# delayed_pulser.net
KiCad netlist of a schematic drawn in EAGLE
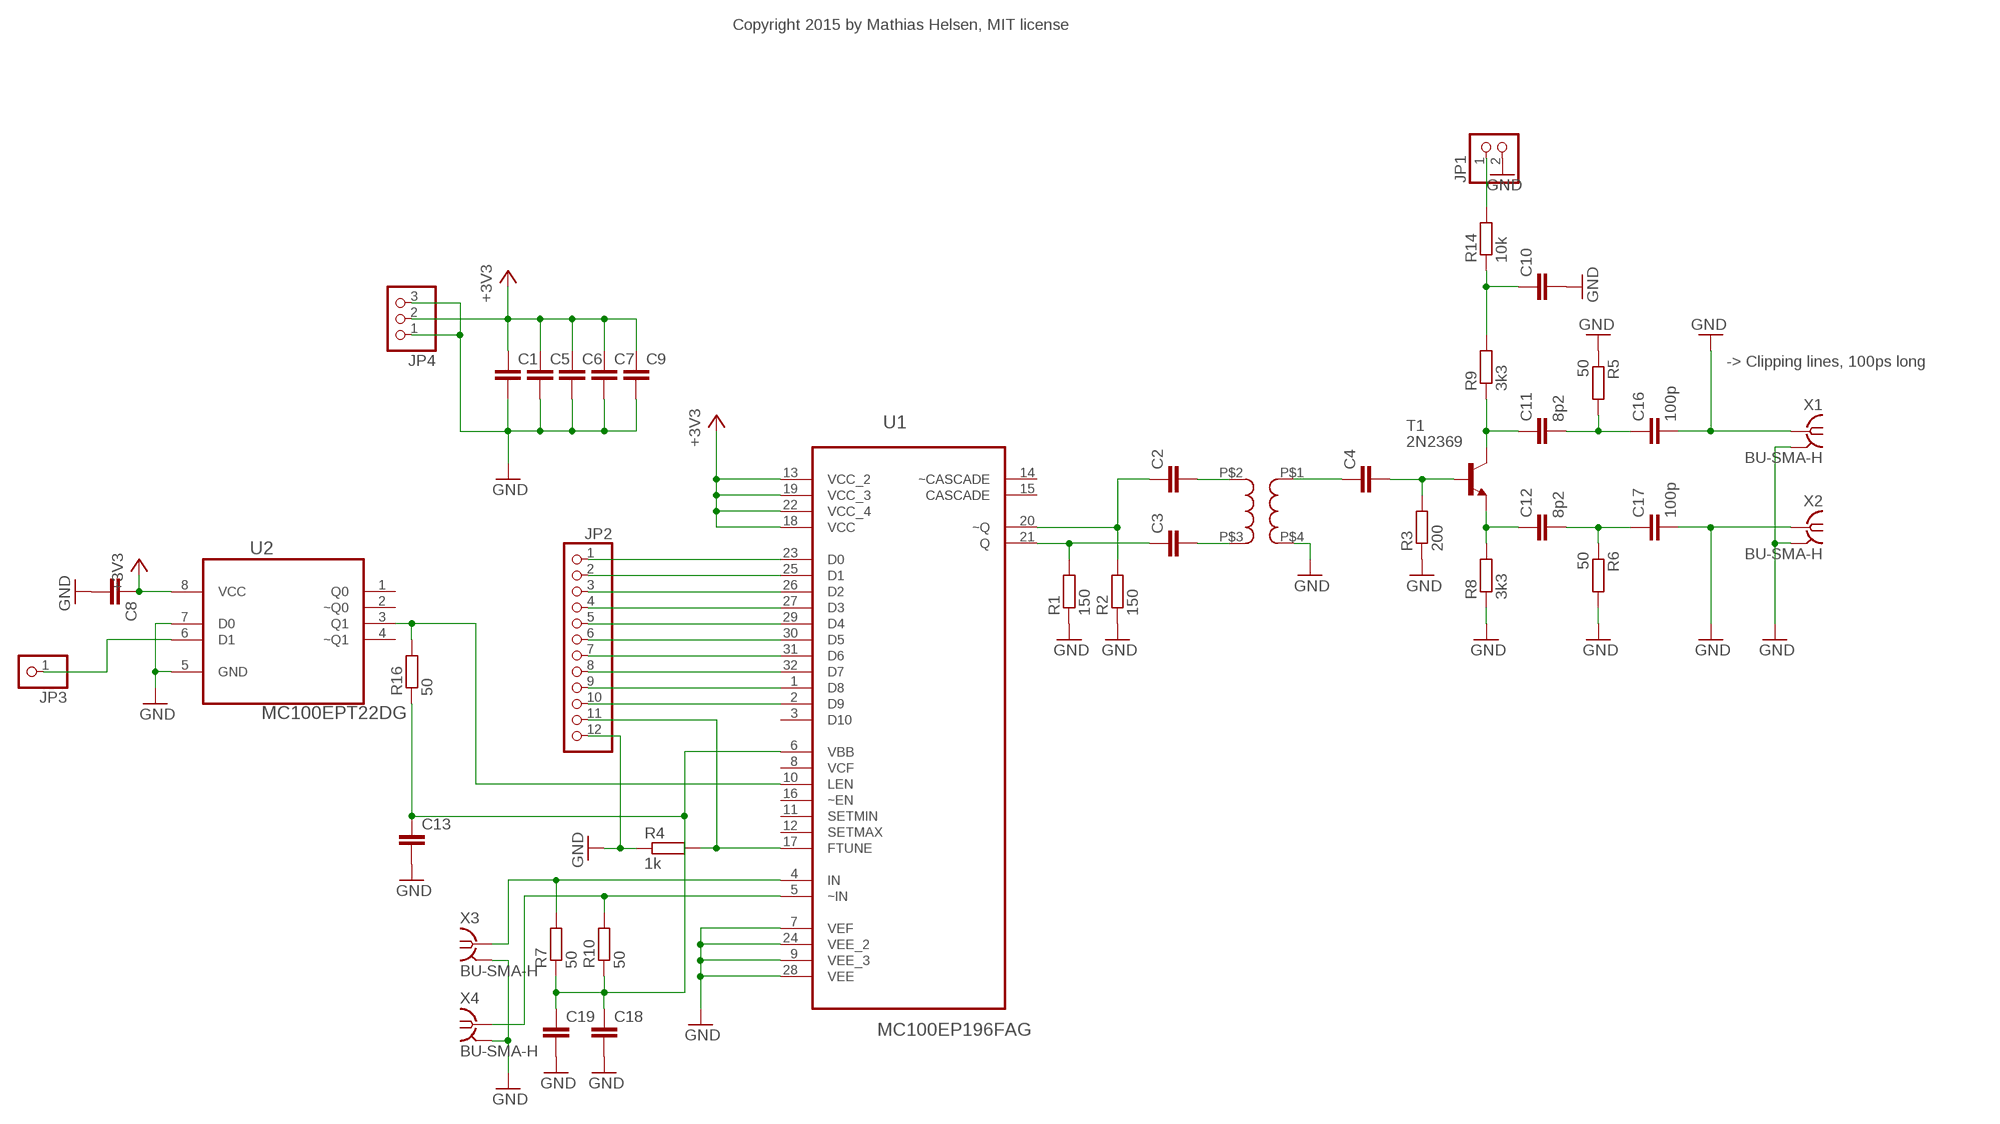
[diagram p0: schematic, sheet 1]

(export (version "E")
  (design (tool "Eeschema 10.0.6"))
  (components
    (comp (ref "C1")
      (value "C-EUC0805")
      (footprint "eagle-import:C0805")
      (libsource (lib "eagle-import") (part "C-EUC0805"))
    )
    (comp (ref "C2")
      (value "C-EUC0805")
      (footprint "eagle-import:C0805")
      (libsource (lib "eagle-import") (part "C-EUC0805"))
    )
    (comp (ref "C3")
      (value "C-EUC0805")
      (footprint "eagle-import:C0805")
      (libsource (lib "eagle-import") (part "C-EUC0805"))
    )
    (comp (ref "C4")
      (value "C-EUC0805")
      (footprint "eagle-import:C0805")
      (libsource (lib "eagle-import") (part "C-EUC0805"))
    )
    (comp (ref "C5")
      (value "C-EUC0805")
      (footprint "eagle-import:C0805")
      (libsource (lib "eagle-import") (part "C-EUC0805"))
    )
    (comp (ref "C6")
      (value "C-EUC0805")
      (footprint "eagle-import:C0805")
      (libsource (lib "eagle-import") (part "C-EUC0805"))
    )
    (comp (ref "C7")
      (value "C-EUC0805")
      (footprint "eagle-import:C0805")
      (libsource (lib "eagle-import") (part "C-EUC0805"))
    )
    (comp (ref "C8")
      (value "C-EUC0805")
      (footprint "eagle-import:C0805")
      (libsource (lib "eagle-import") (part "C-EUC0805"))
    )
    (comp (ref "C9")
      (value "C-EUC1206")
      (footprint "eagle-import:C1206")
      (libsource (lib "eagle-import") (part "C-EUC1206"))
    )
    (comp (ref "C10")
      (value "C-EUC0805")
      (footprint "eagle-import:C0805")
      (libsource (lib "eagle-import") (part "C-EUC0805"))
    )
    (comp (ref "C11")
      (value "8p2")
      (footprint "eagle-import:C0603")
      (libsource (lib "eagle-import") (part "C-EUC0603"))
    )
    (comp (ref "C12")
      (value "8p2")
      (footprint "eagle-import:C0603")
      (libsource (lib "eagle-import") (part "C-EUC0603"))
    )
    (comp (ref "C13")
      (value "C-EUC0805")
      (footprint "eagle-import:C0805")
      (libsource (lib "eagle-import") (part "C-EUC0805"))
    )
    (comp (ref "C16")
      (value "100p")
      (footprint "eagle-import:C0603")
      (libsource (lib "eagle-import") (part "C-EUC0603"))
    )
    (comp (ref "C17")
      (value "100p")
      (footprint "eagle-import:C0603")
      (libsource (lib "eagle-import") (part "C-EUC0603"))
    )
    (comp (ref "C18")
      (value "C-EUC0805")
      (footprint "eagle-import:C0805")
      (libsource (lib "eagle-import") (part "C-EUC0805"))
    )
    (comp (ref "C19")
      (value "C-EUC0805")
      (footprint "eagle-import:C0805")
      (libsource (lib "eagle-import") (part "C-EUC0805"))
    )
    (comp (ref "JP1")
      (value "PINHD-1X2")
      (footprint "eagle-import:1X02")
      (libsource (lib "eagle-import") (part "PINHD-1X2"))
    )
    (comp (ref "JP2")
      (value "PINHD-1X12")
      (footprint "eagle-import:1X12")
      (libsource (lib "eagle-import") (part "PINHD-1X12"))
    )
    (comp (ref "JP3")
      (value "PINHD-1X1")
      (footprint "eagle-import:1X01")
      (libsource (lib "eagle-import") (part "PINHD-1X1"))
    )
    (comp (ref "JP4")
      (value "PINHD-1X3")
      (footprint "eagle-import:1X03")
      (libsource (lib "eagle-import") (part "PINHD-1X3"))
    )
    (comp (ref "R1")
      (value "150")
      (footprint "eagle-import:R0805")
      (libsource (lib "eagle-import") (part "R-EU_R0805"))
    )
    (comp (ref "R2")
      (value "150")
      (footprint "eagle-import:R0805")
      (libsource (lib "eagle-import") (part "R-EU_R0805"))
    )
    (comp (ref "R3")
      (value "200")
      (footprint "eagle-import:R0805")
      (libsource (lib "eagle-import") (part "R-EU_R0805"))
    )
    (comp (ref "R4")
      (value "1k")
      (footprint "eagle-import:R0805")
      (libsource (lib "eagle-import") (part "R-EU_R0805"))
    )
    (comp (ref "R5")
      (value "50")
      (footprint "eagle-import:R0603")
      (libsource (lib "eagle-import") (part "R-EU_R0603"))
    )
    (comp (ref "R6")
      (value "50")
      (footprint "eagle-import:R0603")
      (libsource (lib "eagle-import") (part "R-EU_R0603"))
    )
    (comp (ref "R7")
      (value "50")
      (footprint "eagle-import:R0805")
      (libsource (lib "eagle-import") (part "R-EU_R0805"))
    )
    (comp (ref "R8")
      (value "3k3")
      (footprint "eagle-import:R0805")
      (libsource (lib "eagle-import") (part "R-EU_R0805"))
    )
    (comp (ref "R9")
      (value "3k3")
      (footprint "eagle-import:R0805")
      (libsource (lib "eagle-import") (part "R-EU_R0805"))
    )
    (comp (ref "R10")
      (value "50")
      (footprint "eagle-import:R0805")
      (libsource (lib "eagle-import") (part "R-EU_R0805"))
    )
    (comp (ref "R14")
      (value "10k")
      (footprint "eagle-import:R0805")
      (libsource (lib "eagle-import") (part "R-EU_R0805"))
    )
    (comp (ref "R16")
      (value "50")
      (footprint "eagle-import:R0805")
      (libsource (lib "eagle-import") (part "R-EU_R0805"))
    )
    (comp (ref "T1")
      (value "2N2369")
      (footprint "eagle-import:TO18")
      (libsource (lib "eagle-import") (part "2N2369"))
    )
    (comp (ref "U$1")
      (value "JA4220")
      (footprint "eagle-import:T")
      (libsource (lib "eagle-import") (part "JA4220"))
    )
    (comp (ref "U1")
      (value "MC100EP196FAG")
      (footprint "eagle-import:QFP80P900X900X160-32N")
      (libsource (lib "eagle-import") (part "MC100EP196FAG"))
    )
    (comp (ref "U2")
      (value "MC100EPT22DG")
      (footprint "eagle-import:SOIC127P600X175-8N")
      (libsource (lib "eagle-import") (part "MC100EPT22DG"))
    )
    (comp (ref "X1")
      (value "BU-SMA-H")
      (footprint "eagle-import:BU-SMA-H")
      (libsource (lib "eagle-import") (part "BU-SMA-H"))
    )
    (comp (ref "X2")
      (value "BU-SMA-H")
      (footprint "eagle-import:BU-SMA-H")
      (libsource (lib "eagle-import") (part "BU-SMA-H"))
    )
    (comp (ref "X3")
      (value "BU-SMA-H")
      (footprint "eagle-import:BU-SMA-H")
      (libsource (lib "eagle-import") (part "BU-SMA-H"))
    )
    (comp (ref "X4")
      (value "BU-SMA-H")
      (footprint "eagle-import:BU-SMA-H")
      (libsource (lib "eagle-import") (part "BU-SMA-H"))
    )
  )
  (nets
    (net (code "1") (name "+3V3") (class "Default")
      (node (ref "C1") (pin "1") (pinfunction "1_1") (pintype "passive"))
      (node (ref "C5") (pin "1") (pinfunction "1_1") (pintype "passive"))
      (node (ref "C6") (pin "1") (pinfunction "1_1") (pintype "passive"))
      (node (ref "C7") (pin "1") (pinfunction "1_1") (pintype "passive"))
      (node (ref "C8") (pin "1") (pinfunction "1_1") (pintype "passive"))
      (node (ref "C9") (pin "1") (pinfunction "1_1") (pintype "passive"))
      (node (ref "JP4") (pin "2") (pinfunction "2_2") (pintype "passive"))
      (node (ref "U1") (pin "13") (pinfunction "VCC_2_13") (pintype "power_in"))
      (node (ref "U1") (pin "18") (pinfunction "VCC_18") (pintype "power_in"))
      (node (ref "U1") (pin "19") (pinfunction "VCC_3_19") (pintype "power_in"))
      (node (ref "U1") (pin "22") (pinfunction "VCC_4_22") (pintype "power_in"))
      (node (ref "U2") (pin "8") (pinfunction "VCC_8") (pintype "power_in"))
    )
    (net (code "2") (name "GND") (class "Default")
      (node (ref "C1") (pin "2") (pinfunction "2_2") (pintype "passive"))
      (node (ref "C10") (pin "2") (pinfunction "2_2") (pintype "passive"))
      (node (ref "C13") (pin "2") (pinfunction "2_2") (pintype "passive"))
      (node (ref "C16") (pin "2") (pinfunction "2_2") (pintype "passive"))
      (node (ref "C17") (pin "2") (pinfunction "2_2") (pintype "passive"))
      (node (ref "C18") (pin "2") (pinfunction "2_2") (pintype "passive"))
      (node (ref "C19") (pin "2") (pinfunction "2_2") (pintype "passive"))
      (node (ref "C5") (pin "2") (pinfunction "2_2") (pintype "passive"))
      (node (ref "C6") (pin "2") (pinfunction "2_2") (pintype "passive"))
      (node (ref "C7") (pin "2") (pinfunction "2_2") (pintype "passive"))
      (node (ref "C8") (pin "2") (pinfunction "2_2") (pintype "passive"))
      (node (ref "C9") (pin "2") (pinfunction "2_2") (pintype "passive"))
      (node (ref "JP1") (pin "2") (pinfunction "2_2") (pintype "passive"))
      (node (ref "JP2") (pin "12") (pinfunction "12_12") (pintype "passive"))
      (node (ref "JP4") (pin "1") (pinfunction "1_1") (pintype "passive"))
      (node (ref "JP4") (pin "3") (pinfunction "3_3") (pintype "passive"))
      (node (ref "R1") (pin "1") (pinfunction "1_1") (pintype "passive"))
      (node (ref "R2") (pin "1") (pinfunction "1_1") (pintype "passive"))
      (node (ref "R3") (pin "1") (pinfunction "1_1") (pintype "passive"))
      (node (ref "R4") (pin "1") (pinfunction "1_1") (pintype "passive"))
      (node (ref "R5") (pin "1") (pinfunction "1_1") (pintype "passive"))
      (node (ref "R6") (pin "2") (pinfunction "2_2") (pintype "passive"))
      (node (ref "R8") (pin "1") (pinfunction "1_1") (pintype "passive"))
      (node (ref "U$1") (pin "P$4") (pinfunction "P$4_P$4") (pintype "bidirectional"))
      (node (ref "U1") (pin "24") (pinfunction "VEE_2_24") (pintype "output"))
      (node (ref "U1") (pin "28") (pinfunction "VEE_28") (pintype "passive"))
      (node (ref "U1") (pin "7") (pinfunction "VEF_7") (pintype "input"))
      (node (ref "U1") (pin "9") (pinfunction "VEE_3_9") (pintype "passive"))
      (node (ref "U2") (pin "5") (pinfunction "GND_5") (pintype "passive"))
      (node (ref "U2") (pin "7") (pinfunction "D0_7") (pintype "input"))
      (node (ref "X1") (pin "1") (pinfunction "1_1") (pintype "passive"))
      (node (ref "X1") (pin "2") (pinfunction "2_2") (pintype "passive"))
      (node (ref "X1") (pin "3") (pinfunction "2_3") (pintype "passive"))
      (node (ref "X1") (pin "4") (pinfunction "2_4") (pintype "passive"))
      (node (ref "X1") (pin "5") (pinfunction "2_5") (pintype "passive"))
      (node (ref "X2") (pin "1") (pinfunction "1_1") (pintype "passive"))
      (node (ref "X2") (pin "2") (pinfunction "2_2") (pintype "passive"))
      (node (ref "X2") (pin "3") (pinfunction "2_3") (pintype "passive"))
      (node (ref "X2") (pin "4") (pinfunction "2_4") (pintype "passive"))
      (node (ref "X2") (pin "5") (pinfunction "2_5") (pintype "passive"))
      (node (ref "X3") (pin "2") (pinfunction "2_2") (pintype "passive"))
      (node (ref "X3") (pin "3") (pinfunction "2_3") (pintype "passive"))
      (node (ref "X3") (pin "4") (pinfunction "2_4") (pintype "passive"))
      (node (ref "X3") (pin "5") (pinfunction "2_5") (pintype "passive"))
      (node (ref "X4") (pin "2") (pinfunction "2_2") (pintype "passive"))
      (node (ref "X4") (pin "3") (pinfunction "2_3") (pintype "passive"))
      (node (ref "X4") (pin "4") (pinfunction "2_4") (pintype "passive"))
      (node (ref "X4") (pin "5") (pinfunction "2_5") (pintype "passive"))
    )
    (net (code "3") (name "Net-(C2-Pad2)") (class "Default")
      (node (ref "C2") (pin "2") (pinfunction "2_2") (pintype "passive"))
      (node (ref "U$1") (pin "P$2") (pinfunction "P$2_P$2") (pintype "bidirectional"))
    )
    (net (code "4") (name "Net-(C3-Pad2)") (class "Default")
      (node (ref "C3") (pin "2") (pinfunction "2_2") (pintype "passive"))
      (node (ref "U$1") (pin "P$3") (pinfunction "P$3_P$3") (pintype "bidirectional"))
    )
    (net (code "5") (name "Net-(C4-Pad1)") (class "Default")
      (node (ref "C4") (pin "1") (pinfunction "1_1") (pintype "passive"))
      (node (ref "U$1") (pin "P$1") (pinfunction "P$1_P$1") (pintype "bidirectional"))
    )
    (net (code "6") (name "Net-(C10-Pad1)") (class "Default")
      (node (ref "C10") (pin "1") (pinfunction "1_1") (pintype "passive"))
      (node (ref "R14") (pin "1") (pinfunction "1_1") (pintype "passive"))
      (node (ref "R9") (pin "2") (pinfunction "2_2") (pintype "passive"))
    )
    (net (code "7") (name "Net-(C11-Pad2)") (class "Default")
      (node (ref "C11") (pin "2") (pinfunction "2_2") (pintype "passive"))
      (node (ref "C16") (pin "1") (pinfunction "1_1") (pintype "passive"))
      (node (ref "R5") (pin "2") (pinfunction "2_2") (pintype "passive"))
    )
    (net (code "8") (name "Net-(C12-Pad2)") (class "Default")
      (node (ref "C12") (pin "2") (pinfunction "2_2") (pintype "passive"))
      (node (ref "C17") (pin "1") (pinfunction "1_1") (pintype "passive"))
      (node (ref "R6") (pin "1") (pinfunction "1_1") (pintype "passive"))
    )
    (net (code "9") (name "Net-(JP1-Pad1)") (class "Default")
      (node (ref "JP1") (pin "1") (pinfunction "1_1") (pintype "passive"))
      (node (ref "R14") (pin "2") (pinfunction "2_2") (pintype "passive"))
    )
    (net (code "10") (name "Net-(T1-B)") (class "Default")
      (node (ref "C4") (pin "2") (pinfunction "2_2") (pintype "passive"))
      (node (ref "R3") (pin "2") (pinfunction "2_2") (pintype "passive"))
      (node (ref "T1") (pin "2") (pinfunction "B_2") (pintype "passive"))
    )
    (net (code "11") (name "Net-(T1-C)") (class "Default")
      (node (ref "C11") (pin "1") (pinfunction "1_1") (pintype "passive"))
      (node (ref "R9") (pin "1") (pinfunction "1_1") (pintype "passive"))
      (node (ref "T1") (pin "3") (pinfunction "C_3") (pintype "passive"))
    )
    (net (code "12") (name "Net-(T1-E)") (class "Default")
      (node (ref "C12") (pin "1") (pinfunction "1_1") (pintype "passive"))
      (node (ref "R8") (pin "2") (pinfunction "2_2") (pintype "passive"))
      (node (ref "T1") (pin "1") (pinfunction "E_1") (pintype "passive"))
    )
    (net (code "13") (name "Net-(U1-D0)") (class "Default")
      (node (ref "JP2") (pin "1") (pinfunction "1_1") (pintype "passive"))
      (node (ref "U1") (pin "23") (pinfunction "D0_23") (pintype "input"))
    )
    (net (code "14") (name "Net-(U1-D1)") (class "Default")
      (node (ref "JP2") (pin "2") (pinfunction "2_2") (pintype "passive"))
      (node (ref "U1") (pin "25") (pinfunction "D1_25") (pintype "input"))
    )
    (net (code "15") (name "Net-(U1-D2)") (class "Default")
      (node (ref "JP2") (pin "3") (pinfunction "3_3") (pintype "passive"))
      (node (ref "U1") (pin "26") (pinfunction "D2_26") (pintype "input"))
    )
    (net (code "16") (name "Net-(U1-D3)") (class "Default")
      (node (ref "JP2") (pin "4") (pinfunction "4_4") (pintype "passive"))
      (node (ref "U1") (pin "27") (pinfunction "D3_27") (pintype "input"))
    )
    (net (code "17") (name "Net-(U1-D4)") (class "Default")
      (node (ref "JP2") (pin "5") (pinfunction "5_5") (pintype "passive"))
      (node (ref "U1") (pin "29") (pinfunction "D4_29") (pintype "input"))
    )
    (net (code "18") (name "Net-(U1-D5)") (class "Default")
      (node (ref "JP2") (pin "6") (pinfunction "6_6") (pintype "passive"))
      (node (ref "U1") (pin "30") (pinfunction "D5_30") (pintype "input"))
    )
    (net (code "19") (name "Net-(U1-D6)") (class "Default")
      (node (ref "JP2") (pin "7") (pinfunction "7_7") (pintype "passive"))
      (node (ref "U1") (pin "31") (pinfunction "D6_31") (pintype "input"))
    )
    (net (code "20") (name "Net-(U1-D7)") (class "Default")
      (node (ref "JP2") (pin "8") (pinfunction "8_8") (pintype "passive"))
      (node (ref "U1") (pin "32") (pinfunction "D7_32") (pintype "input"))
    )
    (net (code "21") (name "Net-(U1-D8)") (class "Default")
      (node (ref "JP2") (pin "9") (pinfunction "9_9") (pintype "passive"))
      (node (ref "U1") (pin "1") (pinfunction "D8_1") (pintype "input"))
    )
    (net (code "22") (name "Net-(U1-D9)") (class "Default")
      (node (ref "JP2") (pin "10") (pinfunction "10_10") (pintype "passive"))
      (node (ref "U1") (pin "2") (pinfunction "D9_2") (pintype "input"))
    )
    (net (code "23") (name "Net-(U1-FTUNE)") (class "Default")
      (node (ref "JP2") (pin "11") (pinfunction "11_11") (pintype "passive"))
      (node (ref "R4") (pin "2") (pinfunction "2_2") (pintype "passive"))
      (node (ref "U1") (pin "17") (pinfunction "FTUNE_17") (pintype "input"))
    )
    (net (code "24") (name "Net-(U1-IN)") (class "Default")
      (node (ref "R7") (pin "2") (pinfunction "2_2") (pintype "passive"))
      (node (ref "U1") (pin "4") (pinfunction "IN_4") (pintype "input"))
      (node (ref "X3") (pin "1") (pinfunction "1_1") (pintype "passive"))
    )
    (net (code "25") (name "Net-(U1-LEN)") (class "Default")
      (node (ref "R16") (pin "2") (pinfunction "2_2") (pintype "passive"))
      (node (ref "U1") (pin "10") (pinfunction "LEN_10") (pintype "input"))
      (node (ref "U2") (pin "3") (pinfunction "Q1_3") (pintype "output"))
    )
    (net (code "26") (name "Net-(U1-Q)") (class "Default")
      (node (ref "C3") (pin "1") (pinfunction "1_1") (pintype "passive"))
      (node (ref "R1") (pin "2") (pinfunction "2_2") (pintype "passive"))
      (node (ref "U1") (pin "21") (pinfunction "Q_21") (pintype "output"))
    )
    (net (code "27") (name "Net-(U1-VBB)") (class "Default")
      (node (ref "C13") (pin "1") (pinfunction "1_1") (pintype "passive"))
      (node (ref "C18") (pin "1") (pinfunction "1_1") (pintype "passive"))
      (node (ref "C19") (pin "1") (pinfunction "1_1") (pintype "passive"))
      (node (ref "R10") (pin "1") (pinfunction "1_1") (pintype "passive"))
      (node (ref "R16") (pin "1") (pinfunction "1_1") (pintype "passive"))
      (node (ref "R7") (pin "1") (pinfunction "1_1") (pintype "passive"))
      (node (ref "U1") (pin "6") (pinfunction "VBB_6") (pintype "output"))
    )
    (net (code "28") (name "Net-(U1-~{IN})") (class "Default")
      (node (ref "R10") (pin "2") (pinfunction "2_2") (pintype "passive"))
      (node (ref "U1") (pin "5") (pinfunction "~{IN}_5") (pintype "input"))
      (node (ref "X4") (pin "1") (pinfunction "1_1") (pintype "passive"))
    )
    (net (code "29") (name "Net-(U1-~{Q})") (class "Default")
      (node (ref "C2") (pin "1") (pinfunction "1_1") (pintype "passive"))
      (node (ref "R2") (pin "2") (pinfunction "2_2") (pintype "passive"))
      (node (ref "U1") (pin "20") (pinfunction "~{Q}_20") (pintype "output"))
    )
    (net (code "30") (name "Net-(U2-D1)") (class "Default")
      (node (ref "JP3") (pin "1") (pinfunction "1_1") (pintype "passive"))
      (node (ref "U2") (pin "6") (pinfunction "D1_6") (pintype "input"))
    )
    (net (code "31") (name "unconnected-(U1-CASCADE-Pad15)") (class "Default")
      (node (ref "U1") (pin "15") (pinfunction "CASCADE_15") (pintype "output"))
    )
    (net (code "32") (name "unconnected-(U1-D10-Pad3)") (class "Default")
      (node (ref "U1") (pin "3") (pinfunction "D10_3") (pintype "input"))
    )
    (net (code "33") (name "unconnected-(U1-SETMAX-Pad12)") (class "Default")
      (node (ref "U1") (pin "12") (pinfunction "SETMAX_12") (pintype "input"))
    )
    (net (code "34") (name "unconnected-(U1-SETMIN-Pad11)") (class "Default")
      (node (ref "U1") (pin "11") (pinfunction "SETMIN_11") (pintype "input"))
    )
    (net (code "35") (name "unconnected-(U1-VCF-Pad8)") (class "Default")
      (node (ref "U1") (pin "8") (pinfunction "VCF_8") (pintype "input"))
    )
    (net (code "36") (name "unconnected-(U1-~{CASCADE}-Pad14)") (class "Default")
      (node (ref "U1") (pin "14") (pinfunction "~{CASCADE}_14") (pintype "output"))
    )
    (net (code "37") (name "unconnected-(U1-~{EN}-Pad16)") (class "Default")
      (node (ref "U1") (pin "16") (pinfunction "~{EN}_16") (pintype "output"))
    )
    (net (code "38") (name "unconnected-(U2-Q0-Pad1)") (class "Default")
      (node (ref "U2") (pin "1") (pinfunction "Q0_1") (pintype "output"))
    )
    (net (code "39") (name "unconnected-(U2-~{Q0}-Pad2)") (class "Default")
      (node (ref "U2") (pin "2") (pinfunction "~{Q0}_2") (pintype "output"))
    )
    (net (code "40") (name "unconnected-(U2-~{Q1}-Pad4)") (class "Default")
      (node (ref "U2") (pin "4") (pinfunction "~{Q1}_4") (pintype "output"))
    )
  )
)
